# Page-2.net
KiCad netlist of a schematic drawn in Altium Designer
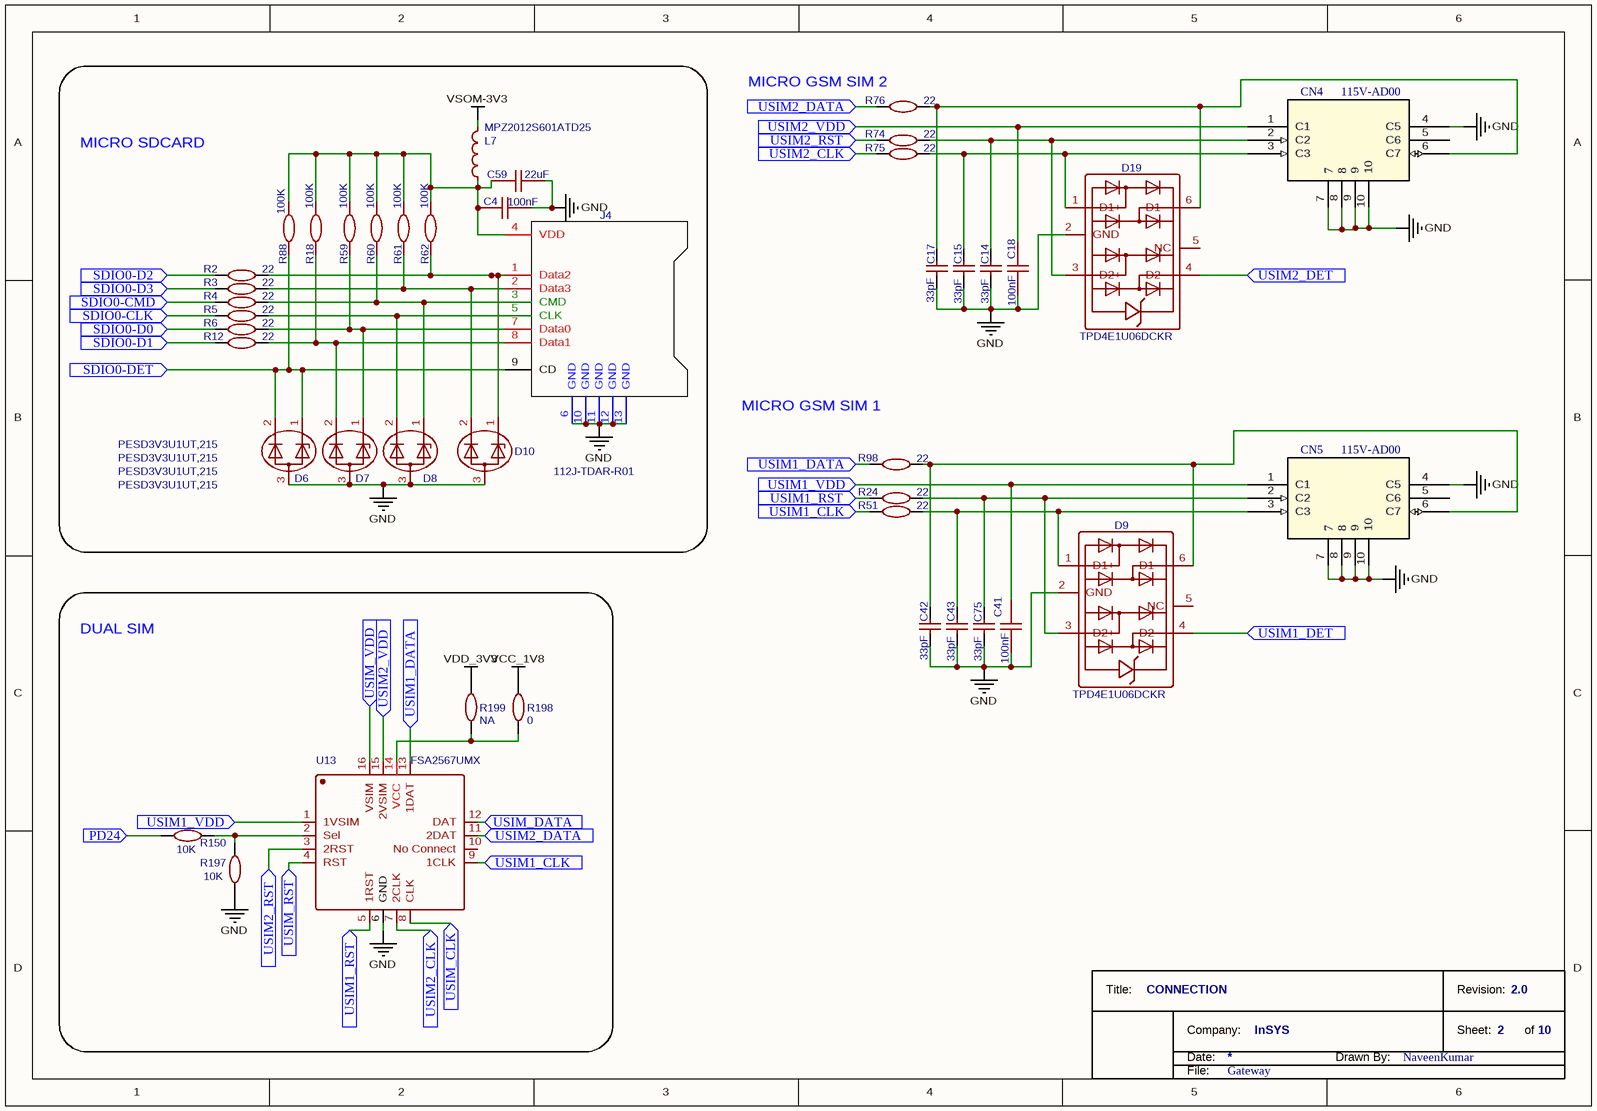
[diagram p0: Page-2.schdoc]

(export (version "E")
  (design (tool "Eeschema 10.0.6"))
  (components
    (comp (ref "*")
      (value "TitleBlock_1")
      (description "TitleBlock  No-2")
      (fields (field (name "DRAWN BY") "*"))
      (libsource (lib "GateWay_AllwinnerV2") (part "TitleBlock_1"))
    )
    (comp (ref "C4")
      (value "100nF")
      (footprint "GWAY_Capacitor_0603")
      (fields (field (name "MANUFACTURER") "SAMSUNG") (field (name "MANUFACTURER PART") "CL10B104KB8NNNC"))
      (libsource (lib "altium-import") (part "root_2_100nF_"))
    )
    (comp (ref "C14")
      (value "33pF")
      (footprint "GWAY_Capacitor_0603")
      (fields (field (name "MANUFACTURER PART") "CL10C330JB8NNNC") (field (name "MANUFACTURER") "SAMSUNG"))
      (libsource (lib "altium-import") (part "root_1_33pF_"))
    )
    (comp (ref "C15")
      (value "33pF")
      (footprint "GWAY_Capacitor_0603")
      (fields (field (name "MANUFACTURER PART") "CL10C330JB8NNNC") (field (name "MANUFACTURER") "SAMSUNG"))
      (libsource (lib "altium-import") (part "root_1_33pF_"))
    )
    (comp (ref "C17")
      (value "33pF")
      (footprint "GWAY_Capacitor_0603")
      (fields (field (name "MANUFACTURER PART") "CL10C330JB8NNNC") (field (name "MANUFACTURER") "SAMSUNG"))
      (libsource (lib "altium-import") (part "root_1_33pF_"))
    )
    (comp (ref "C18")
      (value "100nF")
      (footprint "GWAY_Capacitor_0603")
      (fields (field (name "MANUFACTURER") "SAMSUNG") (field (name "MANUFACTURER PART") "CL10B104KB8NNNC"))
      (libsource (lib "altium-import") (part "root_3_100nF_"))
    )
    (comp (ref "C41")
      (value "100nF")
      (footprint "GWAY_Capacitor_0603")
      (fields (field (name "MANUFACTURER") "SAMSUNG") (field (name "MANUFACTURER PART") "CL10B104KB8NNNC"))
      (libsource (lib "altium-import") (part "root_3_100nF_"))
    )
    (comp (ref "C42")
      (value "33pF")
      (footprint "GWAY_Capacitor_0603")
      (fields (field (name "MANUFACTURER PART") "CL10C330JB8NNNC") (field (name "MANUFACTURER") "SAMSUNG"))
      (libsource (lib "altium-import") (part "root_1_33pF_"))
    )
    (comp (ref "C43")
      (value "33pF")
      (footprint "GWAY_Capacitor_0603")
      (fields (field (name "MANUFACTURER PART") "CL10C330JB8NNNC") (field (name "MANUFACTURER") "SAMSUNG"))
      (libsource (lib "altium-import") (part "root_1_33pF_"))
    )
    (comp (ref "C59")
      (value "22uF")
      (footprint "GWAY_Capacitor_0805")
      (fields (field (name "MANUFACTURER") "SAMSUNG") (field (name "MANUFACTURER PART") "CL21A226MQQNNNE"))
      (libsource (lib "altium-import") (part "root_2_22uF_"))
    )
    (comp (ref "C75")
      (value "33pF")
      (footprint "GWAY_Capacitor_0603")
      (fields (field (name "MANUFACTURER PART") "CL10C330JB8NNNC") (field (name "MANUFACTURER") "SAMSUNG"))
      (libsource (lib "altium-import") (part "root_1_33pF_"))
    )
    (comp (ref "CN4")
      (value "115V-AD00")
      (footprint "GWAY_115V-AD00_ATT")
      (description "No Description Available")
      (fields (field (name "COPYRIGHT") "Copyright (C) 2023 Ultra Librarian. All rights reserved."))
      (libsource (lib "GateWay_AllwinnerV2") (part "115V-AD00"))
    )
    (comp (ref "CN5")
      (value "115V-AD00")
      (footprint "GWAY_115V-AD00_ATT")
      (description "No Description Available")
      (fields (field (name "COPYRIGHT") "Copyright (C) 2023 Ultra Librarian. All rights reserved."))
      (libsource (lib "GateWay_AllwinnerV2") (part "115V-AD00"))
    )
    (comp (ref "D6")
      (value "PESD3V3U1UT,215")
      (footprint "GWAY_SOT23-3PIN")
      (fields (field (name "MANUFACTURER") "Nexperia") (field (name "CONTRIBUTOR") "LCSC"))
      (libsource (lib "altium-import") (part "root_2_PESD3V3U1UT,215_"))
    )
    (comp (ref "D7")
      (value "PESD3V3U1UT,215")
      (footprint "GWAY_SOT23-3PIN")
      (fields (field (name "MANUFACTURER") "Nexperia") (field (name "CONTRIBUTOR") "LCSC"))
      (libsource (lib "altium-import") (part "root_2_PESD3V3U1UT,215_"))
    )
    (comp (ref "D8")
      (value "PESD3V3U1UT,215")
      (footprint "GWAY_SOT23-3PIN")
      (fields (field (name "MANUFACTURER") "Nexperia") (field (name "CONTRIBUTOR") "LCSC"))
      (libsource (lib "altium-import") (part "root_2_PESD3V3U1UT,215_"))
    )
    (comp (ref "D9")
      (value "TPD4E1U06DCKR")
      (footprint "GWAY_SC70-6PIN")
      (fields (field (name "MANUFACTURER") "Texas Instruments") (field (name "CONTRIBUTOR") "LCSC"))
      (libsource (lib "altium-import") (part "root_3_TPD4E1U06DCKR_"))
    )
    (comp (ref "D10")
      (value "PESD3V3U1UT,215")
      (footprint "GWAY_SOT23-3PIN")
      (fields (field (name "MANUFACTURER") "Nexperia") (field (name "CONTRIBUTOR") "LCSC"))
      (libsource (lib "altium-import") (part "root_2_PESD3V3U1UT,215_"))
    )
    (comp (ref "D19")
      (value "TPD4E1U06DCKR")
      (footprint "GWAY_SC70-6PIN")
      (fields (field (name "MANUFACTURER") "Texas Instruments") (field (name "CONTRIBUTOR") "LCSC"))
      (libsource (lib "altium-import") (part "root_3_TPD4E1U06DCKR_"))
    )
    (comp (ref "J4")
      (value "112J-TDAR-R01")
      (footprint "GWAY_12JTDARR01")
      (fields (field (name "CONTRIBUTOR") "Arkadiusz Karaś"))
      (libsource (lib "altium-import") (part "root_0_112J-TDAR-R01_"))
    )
    (comp (ref "L7")
      (value "MPZ2012S601ATD25")
      (footprint "GWAY_FerriteeBEAD_0805_C2012X105N")
      (fields (field (name "MANUFACTURER") "TDK") (field (name "CONTRIBUTOR") "LCSC"))
      (libsource (lib "altium-import") (part "root_1_MPZ2012S601ATD25_"))
    )
    (comp (ref "R2")
      (value "22")
      (footprint "GWAY_Resistor_0603")
      (fields (field (name "MANUFACTURER") "YAGEO") (field (name "MANUFACTURER PART") "RC0603FR-0722RL"))
      (libsource (lib "altium-import") (part "root_2_22_"))
    )
    (comp (ref "R3")
      (value "22")
      (footprint "GWAY_Resistor_0603")
      (fields (field (name "MANUFACTURER") "YAGEO") (field (name "MANUFACTURER PART") "RC0603FR-0722RL"))
      (libsource (lib "altium-import") (part "root_2_22_"))
    )
    (comp (ref "R4")
      (value "22")
      (footprint "GWAY_Resistor_0603")
      (fields (field (name "MANUFACTURER") "YAGEO") (field (name "MANUFACTURER PART") "RC0603FR-0722RL"))
      (libsource (lib "altium-import") (part "root_2_22_"))
    )
    (comp (ref "R5")
      (value "22")
      (footprint "GWAY_Resistor_0603")
      (fields (field (name "MANUFACTURER") "YAGEO") (field (name "MANUFACTURER PART") "RC0603FR-0722RL"))
      (libsource (lib "altium-import") (part "root_2_22_"))
    )
    (comp (ref "R6")
      (value "22")
      (footprint "GWAY_Resistor_0603")
      (fields (field (name "MANUFACTURER") "YAGEO") (field (name "MANUFACTURER PART") "RC0603FR-0722RL"))
      (libsource (lib "altium-import") (part "root_2_22_"))
    )
    (comp (ref "R12")
      (value "22")
      (footprint "GWAY_Resistor_0603")
      (fields (field (name "MANUFACTURER") "YAGEO") (field (name "MANUFACTURER PART") "RC0603FR-0722RL"))
      (libsource (lib "altium-import") (part "root_2_22_"))
    )
    (comp (ref "R18")
      (value "100K")
      (footprint "GWAY_Resistor_0603")
      (fields
        (field (name "MANUFACTURER") "YAGEO")
        (field (name "MANUFACTURER PART") "RC0603FR-07100KL")
        (field (name "CONTRIBUTOR") "LCSC")
      )
      (libsource (lib "altium-import") (part "root_3_100K_"))
    )
    (comp (ref "R24")
      (value "22")
      (footprint "GWAY_Resistor_0603")
      (fields (field (name "MANUFACTURER") "YAGEO") (field (name "MANUFACTURER PART") "RC0603FR-0722RL"))
      (libsource (lib "altium-import") (part "root_0_22_"))
    )
    (comp (ref "R51")
      (value "22")
      (footprint "GWAY_Resistor_0603")
      (fields (field (name "MANUFACTURER") "YAGEO") (field (name "MANUFACTURER PART") "RC0603FR-0722RL"))
      (libsource (lib "altium-import") (part "root_0_22_"))
    )
    (comp (ref "R59")
      (value "100K")
      (footprint "GWAY_Resistor_0603")
      (fields
        (field (name "MANUFACTURER") "YAGEO")
        (field (name "MANUFACTURER PART") "RC0603FR-07100KL")
        (field (name "CONTRIBUTOR") "LCSC")
      )
      (libsource (lib "altium-import") (part "root_3_100K_"))
    )
    (comp (ref "R60")
      (value "100K")
      (footprint "GWAY_Resistor_0603")
      (fields
        (field (name "MANUFACTURER") "YAGEO")
        (field (name "MANUFACTURER PART") "RC0603FR-07100KL")
        (field (name "CONTRIBUTOR") "LCSC")
      )
      (libsource (lib "altium-import") (part "root_3_100K_"))
    )
    (comp (ref "R61")
      (value "100K")
      (footprint "GWAY_Resistor_0603")
      (fields
        (field (name "MANUFACTURER") "YAGEO")
        (field (name "MANUFACTURER PART") "RC0603FR-07100KL")
        (field (name "CONTRIBUTOR") "LCSC")
      )
      (libsource (lib "altium-import") (part "root_3_100K_"))
    )
    (comp (ref "R62")
      (value "100K")
      (footprint "GWAY_Resistor_0603")
      (fields
        (field (name "MANUFACTURER") "YAGEO")
        (field (name "MANUFACTURER PART") "RC0603FR-07100KL")
        (field (name "CONTRIBUTOR") "LCSC")
      )
      (libsource (lib "altium-import") (part "root_3_100K_"))
    )
    (comp (ref "R74")
      (value "22")
      (footprint "GWAY_Resistor_0603")
      (fields (field (name "MANUFACTURER") "YAGEO") (field (name "MANUFACTURER PART") "RC0603FR-0722RL"))
      (libsource (lib "altium-import") (part "root_0_22_"))
    )
    (comp (ref "R75")
      (value "22")
      (footprint "GWAY_Resistor_0603")
      (fields (field (name "MANUFACTURER") "YAGEO") (field (name "MANUFACTURER PART") "RC0603FR-0722RL"))
      (libsource (lib "altium-import") (part "root_0_22_"))
    )
    (comp (ref "R76")
      (value "22")
      (footprint "GWAY_Resistor_0603")
      (fields (field (name "MANUFACTURER") "YAGEO") (field (name "MANUFACTURER PART") "RC0603FR-0722RL"))
      (libsource (lib "altium-import") (part "root_0_22_"))
    )
    (comp (ref "R88")
      (value "100K")
      (footprint "GWAY_Resistor_0603")
      (fields
        (field (name "MANUFACTURER") "YAGEO")
        (field (name "MANUFACTURER PART") "RC0603FR-07100KL")
        (field (name "CONTRIBUTOR") "LCSC")
      )
      (libsource (lib "altium-import") (part "root_3_100K_"))
    )
    (comp (ref "R98")
      (value "22")
      (footprint "GWAY_Resistor_0603")
      (fields (field (name "MANUFACTURER") "YAGEO") (field (name "MANUFACTURER PART") "RC0603FR-0722RL"))
      (libsource (lib "altium-import") (part "root_0_22_"))
    )
    (comp (ref "R150")
      (value "10K")
      (footprint "GWAY_Resistor_0603")
      (fields (field (name "MANUFACTURER") "YAGEO") (field (name "MANUFACTURER PART") "RC0603JR-0710KL"))
      (libsource (lib "altium-import") (part "root_2_10K_"))
    )
    (comp (ref "R197")
      (value "10K")
      (footprint "GWAY_Resistor_0603")
      (fields (field (name "MANUFACTURER") "YAGEO") (field (name "MANUFACTURER PART") "RC0603JR-0710KL"))
      (libsource (lib "altium-import") (part "root_1_10K_"))
    )
    (comp (ref "R198")
      (value "0")
      (footprint "GWAY_Resistor_0603")
      (fields (field (name "MANUFACTURER") "YAGEO") (field (name "MANUFACTURER PART") "RC0603FR-070RL"))
      (libsource (lib "altium-import") (part "root_1_0_"))
    )
    (comp (ref "R199")
      (value "NA")
      (footprint "GWAY_Resistor_0603")
      (fields (field (name "MANUFACTURER") "YAGEO") (field (name "MANUFACTURER PART") "RC0603FR-070RL"))
      (libsource (lib "altium-import") (part "root_1_NA_"))
    )
    (comp (ref "U13")
      (value "FSA2567UMX")
      (footprint "GWAY_FSA2567UMX")
      (fields (field (name "MANUFACTURER") "ON Semicon") (field (name "CONTRIBUTOR") "LCSC"))
      (libsource (lib "altium-import") (part "root_0_FSA2567UMX_"))
    )
  )
  (nets
    (net (code "1") (name "/PD24") (class "Default")
      (node (ref "R150") (pin "2") (pinfunction "2_2") (pintype "passive"))
    )
    (net (code "2") (name "/SDIO0-CLK") (class "Default")
      (node (ref "R5") (pin "2") (pinfunction "2_2") (pintype "passive"))
    )
    (net (code "3") (name "/SDIO0-CMD") (class "Default")
      (node (ref "R4") (pin "2") (pinfunction "2_2") (pintype "passive"))
    )
    (net (code "4") (name "/SDIO0-D0") (class "Default")
      (node (ref "R6") (pin "2") (pinfunction "2_2") (pintype "passive"))
    )
    (net (code "5") (name "/SDIO0-D1") (class "Default")
      (node (ref "R12") (pin "2") (pinfunction "2_2") (pintype "passive"))
    )
    (net (code "6") (name "/SDIO0-D2") (class "Default")
      (node (ref "R2") (pin "2") (pinfunction "2_2") (pintype "passive"))
    )
    (net (code "7") (name "/SDIO0-D3") (class "Default")
      (node (ref "R3") (pin "2") (pinfunction "2_2") (pintype "passive"))
    )
    (net (code "8") (name "/SDIO0-DET") (class "Default")
      (node (ref "D6") (pin "1") (pinfunction "1_1") (pintype "passive"))
      (node (ref "D6") (pin "2") (pinfunction "2_2") (pintype "passive"))
      (node (ref "J4") (pin "9") (pinfunction "CD_9") (pintype "passive"))
      (node (ref "R88") (pin "2") (pinfunction "2_2") (pintype "passive"))
    )
    (net (code "9") (name "/USIM1_CLK") (class "Default")
      (node (ref "R51") (pin "1") (pinfunction "1_1") (pintype "passive"))
      (node (ref "U13") (pin "9") (pinfunction "1CLK_9") (pintype "passive"))
    )
    (net (code "10") (name "/USIM1_DATA") (class "Default")
      (node (ref "R98") (pin "1") (pinfunction "1_1") (pintype "passive"))
      (node (ref "U13") (pin "13") (pinfunction "1DAT_13") (pintype "passive"))
    )
    (net (code "11") (name "/USIM1_DET") (class "Default")
      (node (ref "D9") (pin "4") (pinfunction "D2-_4") (pintype "passive"))
    )
    (net (code "12") (name "/USIM1_RST") (class "Default")
      (node (ref "R24") (pin "1") (pinfunction "1_1") (pintype "passive"))
      (node (ref "U13") (pin "5") (pinfunction "1RST_5") (pintype "passive"))
    )
    (net (code "13") (name "/USIM1_VDD") (class "Default")
      (node (ref "C41") (pin "1") (pinfunction "1_1") (pintype "passive"))
      (node (ref "CN5") (pin "1") (pinfunction "C1_1") (pintype "power_in"))
      (node (ref "U13") (pin "1") (pinfunction "1VSIM_1") (pintype "passive"))
    )
    (net (code "14") (name "/USIM2_CLK") (class "Default")
      (node (ref "R75") (pin "1") (pinfunction "1_1") (pintype "passive"))
      (node (ref "U13") (pin "7") (pinfunction "2CLK_7") (pintype "passive"))
    )
    (net (code "15") (name "/USIM2_DATA") (class "Default")
      (node (ref "R76") (pin "1") (pinfunction "1_1") (pintype "passive"))
      (node (ref "U13") (pin "11") (pinfunction "2DAT_11") (pintype "passive"))
    )
    (net (code "16") (name "/USIM2_DET") (class "Default")
      (node (ref "D19") (pin "4") (pinfunction "D2-_4") (pintype "passive"))
    )
    (net (code "17") (name "/USIM2_RST") (class "Default")
      (node (ref "R74") (pin "1") (pinfunction "1_1") (pintype "passive"))
      (node (ref "U13") (pin "3") (pinfunction "2RST_3") (pintype "passive"))
    )
    (net (code "18") (name "/USIM2_VDD") (class "Default")
      (node (ref "C18") (pin "1") (pinfunction "1_1") (pintype "passive"))
      (node (ref "CN4") (pin "1") (pinfunction "C1_1") (pintype "power_in"))
      (node (ref "U13") (pin "15") (pinfunction "2VSIM_15") (pintype "passive"))
    )
    (net (code "19") (name "/USIM_CLK") (class "Default")
      (node (ref "U13") (pin "8") (pinfunction "CLK_8") (pintype "passive"))
    )
    (net (code "20") (name "/USIM_DATA") (class "Default")
      (node (ref "U13") (pin "12") (pinfunction "DAT_12") (pintype "passive"))
    )
    (net (code "21") (name "/USIM_RST") (class "Default")
      (node (ref "U13") (pin "4") (pinfunction "RST_4") (pintype "passive"))
    )
    (net (code "22") (name "/USIM_VDD") (class "Default")
      (node (ref "U13") (pin "16") (pinfunction "VSIM_16") (pintype "passive"))
    )
    (net (code "23") (name "GND") (class "Default")
      (node (ref "C14") (pin "1") (pinfunction "1_1") (pintype "passive"))
      (node (ref "C15") (pin "1") (pinfunction "1_1") (pintype "passive"))
      (node (ref "C17") (pin "1") (pinfunction "1_1") (pintype "passive"))
      (node (ref "C18") (pin "2") (pinfunction "2_2") (pintype "passive"))
      (node (ref "C4") (pin "1") (pinfunction "1_1") (pintype "passive"))
      (node (ref "C41") (pin "2") (pinfunction "2_2") (pintype "passive"))
      (node (ref "C42") (pin "1") (pinfunction "1_1") (pintype "passive"))
      (node (ref "C43") (pin "1") (pinfunction "1_1") (pintype "passive"))
      (node (ref "C59") (pin "1") (pinfunction "1_1") (pintype "passive"))
      (node (ref "C75") (pin "1") (pinfunction "1_1") (pintype "passive"))
      (node (ref "CN4") (pin "10") (pinfunction "10_10") (pintype "passive"))
      (node (ref "CN4") (pin "4") (pinfunction "C5_4") (pintype "power_in"))
      (node (ref "CN4") (pin "7") (pinfunction "7_7") (pintype "passive"))
      (node (ref "CN4") (pin "8") (pinfunction "8_8") (pintype "passive"))
      (node (ref "CN4") (pin "9") (pinfunction "9_9") (pintype "passive"))
      (node (ref "CN5") (pin "10") (pinfunction "10_10") (pintype "passive"))
      (node (ref "CN5") (pin "4") (pinfunction "C5_4") (pintype "power_in"))
      (node (ref "CN5") (pin "7") (pinfunction "7_7") (pintype "passive"))
      (node (ref "CN5") (pin "8") (pinfunction "8_8") (pintype "passive"))
      (node (ref "CN5") (pin "9") (pinfunction "9_9") (pintype "passive"))
      (node (ref "D10") (pin "3") (pinfunction "3_3") (pintype "passive"))
      (node (ref "D19") (pin "2") (pinfunction "GND_2") (pintype "passive"))
      (node (ref "D6") (pin "3") (pinfunction "3_3") (pintype "passive"))
      (node (ref "D7") (pin "3") (pinfunction "3_3") (pintype "passive"))
      (node (ref "D8") (pin "3") (pinfunction "3_3") (pintype "passive"))
      (node (ref "D9") (pin "2") (pinfunction "GND_2") (pintype "passive"))
      (node (ref "J4") (pin "10") (pinfunction "GND_10") (pintype "passive"))
      (node (ref "J4") (pin "11") (pinfunction "GND_11") (pintype "passive"))
      (node (ref "J4") (pin "12") (pinfunction "GND_12") (pintype "passive"))
      (node (ref "J4") (pin "13") (pinfunction "GND_13") (pintype "passive"))
      (node (ref "J4") (pin "6") (pinfunction "GND_6") (pintype "passive"))
      (node (ref "R197") (pin "1") (pinfunction "1_1") (pintype "passive"))
      (node (ref "U13") (pin "6") (pinfunction "GND_6") (pintype "passive"))
    )
    (net (code "24") (name "Net-(CN4-C2)") (class "Default")
      (node (ref "C14") (pin "2") (pinfunction "2_2") (pintype "passive"))
      (node (ref "CN4") (pin "2") (pinfunction "C2_2") (pintype "input"))
      (node (ref "D19") (pin "3") (pinfunction "D2+_3") (pintype "passive"))
      (node (ref "R74") (pin "2") (pinfunction "2_2") (pintype "passive"))
    )
    (net (code "25") (name "Net-(CN4-C3)") (class "Default")
      (node (ref "C15") (pin "2") (pinfunction "2_2") (pintype "passive"))
      (node (ref "CN4") (pin "3") (pinfunction "C3_3") (pintype "input"))
      (node (ref "D19") (pin "1") (pinfunction "D1+_1") (pintype "passive"))
      (node (ref "R75") (pin "2") (pinfunction "2_2") (pintype "passive"))
    )
    (net (code "26") (name "Net-(CN4-C7)") (class "Default")
      (node (ref "C17") (pin "2") (pinfunction "2_2") (pintype "passive"))
      (node (ref "CN4") (pin "6") (pinfunction "C7_6") (pintype "bidirectional"))
      (node (ref "D19") (pin "6") (pinfunction "D1-_6") (pintype "passive"))
      (node (ref "R76") (pin "2") (pinfunction "2_2") (pintype "passive"))
    )
    (net (code "27") (name "Net-(CN5-C2)") (class "Default")
      (node (ref "C75") (pin "2") (pinfunction "2_2") (pintype "passive"))
      (node (ref "CN5") (pin "2") (pinfunction "C2_2") (pintype "input"))
      (node (ref "D9") (pin "3") (pinfunction "D2+_3") (pintype "passive"))
      (node (ref "R24") (pin "2") (pinfunction "2_2") (pintype "passive"))
    )
    (net (code "28") (name "Net-(CN5-C3)") (class "Default")
      (node (ref "C43") (pin "2") (pinfunction "2_2") (pintype "passive"))
      (node (ref "CN5") (pin "3") (pinfunction "C3_3") (pintype "input"))
      (node (ref "D9") (pin "1") (pinfunction "D1+_1") (pintype "passive"))
      (node (ref "R51") (pin "2") (pinfunction "2_2") (pintype "passive"))
    )
    (net (code "29") (name "Net-(CN5-C7)") (class "Default")
      (node (ref "C42") (pin "2") (pinfunction "2_2") (pintype "passive"))
      (node (ref "CN5") (pin "6") (pinfunction "C7_6") (pintype "bidirectional"))
      (node (ref "D9") (pin "6") (pinfunction "D1-_6") (pintype "passive"))
      (node (ref "R98") (pin "2") (pinfunction "2_2") (pintype "passive"))
    )
    (net (code "30") (name "Net-(J4-CLK)") (class "Default")
      (node (ref "D8") (pin "2") (pinfunction "2_2") (pintype "passive"))
      (node (ref "J4") (pin "5") (pinfunction "CLK_5") (pintype "passive"))
      (node (ref "R5") (pin "1") (pinfunction "1_1") (pintype "passive"))
    )
    (net (code "31") (name "Net-(J4-CMD)") (class "Default")
      (node (ref "D8") (pin "1") (pinfunction "1_1") (pintype "passive"))
      (node (ref "J4") (pin "3") (pinfunction "CMD_3") (pintype "passive"))
      (node (ref "R4") (pin "1") (pinfunction "1_1") (pintype "passive"))
      (node (ref "R60") (pin "2") (pinfunction "2_2") (pintype "passive"))
    )
    (net (code "32") (name "Net-(J4-Data0)") (class "Default")
      (node (ref "D7") (pin "1") (pinfunction "1_1") (pintype "passive"))
      (node (ref "J4") (pin "7") (pinfunction "Data0_7") (pintype "passive"))
      (node (ref "R59") (pin "2") (pinfunction "2_2") (pintype "passive"))
      (node (ref "R6") (pin "1") (pinfunction "1_1") (pintype "passive"))
    )
    (net (code "33") (name "Net-(J4-Data1)") (class "Default")
      (node (ref "D7") (pin "2") (pinfunction "2_2") (pintype "passive"))
      (node (ref "J4") (pin "8") (pinfunction "Data1_8") (pintype "passive"))
      (node (ref "R12") (pin "1") (pinfunction "1_1") (pintype "passive"))
      (node (ref "R18") (pin "2") (pinfunction "2_2") (pintype "passive"))
    )
    (net (code "34") (name "Net-(J4-Data2)") (class "Default")
      (node (ref "D10") (pin "1") (pinfunction "1_1") (pintype "passive"))
      (node (ref "J4") (pin "1") (pinfunction "Data2_1") (pintype "passive"))
      (node (ref "R2") (pin "1") (pinfunction "1_1") (pintype "passive"))
      (node (ref "R62") (pin "2") (pinfunction "2_2") (pintype "passive"))
    )
    (net (code "35") (name "Net-(J4-Data3)") (class "Default")
      (node (ref "D10") (pin "2") (pinfunction "2_2") (pintype "passive"))
      (node (ref "J4") (pin "2") (pinfunction "Data3_2") (pintype "passive"))
      (node (ref "R3") (pin "1") (pinfunction "1_1") (pintype "passive"))
      (node (ref "R61") (pin "2") (pinfunction "2_2") (pintype "passive"))
    )
    (net (code "36") (name "Net-(J4-VDD)") (class "Default")
      (node (ref "C4") (pin "2") (pinfunction "2_2") (pintype "passive"))
      (node (ref "C59") (pin "2") (pinfunction "2_2") (pintype "passive"))
      (node (ref "J4") (pin "4") (pinfunction "VDD_4") (pintype "passive"))
      (node (ref "L7") (pin "1") (pinfunction "1_1") (pintype "passive"))
      (node (ref "R18") (pin "1") (pinfunction "1_1") (pintype "passive"))
      (node (ref "R59") (pin "1") (pinfunction "1_1") (pintype "passive"))
      (node (ref "R60") (pin "1") (pinfunction "1_1") (pintype "passive"))
      (node (ref "R61") (pin "1") (pinfunction "1_1") (pintype "passive"))
      (node (ref "R62") (pin "1") (pinfunction "1_1") (pintype "passive"))
      (node (ref "R88") (pin "1") (pinfunction "1_1") (pintype "passive"))
    )
    (net (code "37") (name "Net-(U13-Sel)") (class "Default")
      (node (ref "R150") (pin "1") (pinfunction "1_1") (pintype "passive"))
      (node (ref "R197") (pin "2") (pinfunction "2_2") (pintype "passive"))
      (node (ref "U13") (pin "2") (pinfunction "Sel_2") (pintype "passive"))
    )
    (net (code "38") (name "Net-(U13-VCC)") (class "Default")
      (node (ref "R198") (pin "1") (pinfunction "1_1") (pintype "passive"))
      (node (ref "R199") (pin "1") (pinfunction "1_1") (pintype "passive"))
      (node (ref "U13") (pin "14") (pinfunction "VCC_14") (pintype "passive"))
    )
    (net (code "39") (name "VCC_1V8") (class "Default")
      (node (ref "R198") (pin "2") (pinfunction "2_2") (pintype "passive"))
    )
    (net (code "40") (name "VDD_3V3") (class "Default")
      (node (ref "R199") (pin "2") (pinfunction "2_2") (pintype "passive"))
    )
    (net (code "41") (name "VSOM-3V3") (class "Default")
      (node (ref "L7") (pin "2") (pinfunction "2_2") (pintype "passive"))
    )
    (net (code "42") (name "unconnected-(CN4-C6-Pad5)") (class "Default")
      (node (ref "CN4") (pin "5") (pinfunction "C6_5") (pintype "power_in"))
    )
    (net (code "43") (name "unconnected-(CN5-C6-Pad5)") (class "Default")
      (node (ref "CN5") (pin "5") (pinfunction "C6_5") (pintype "power_in"))
    )
    (net (code "44") (name "unconnected-(D9-NC-Pad5)") (class "Default")
      (node (ref "D9") (pin "5") (pinfunction "NC_5") (pintype "passive"))
    )
    (net (code "45") (name "unconnected-(D19-NC-Pad5)") (class "Default")
      (node (ref "D19") (pin "5") (pinfunction "NC_5") (pintype "passive"))
    )
    (net (code "46") (name "unconnected-(U13-No_Connect-Pad10)") (class "Default")
      (node (ref "U13") (pin "10") (pinfunction "No_Connect_10") (pintype "passive"))
    )
  )
)
